# ultrasonic.net
KiCad netlist of a schematic drawn in EAGLE
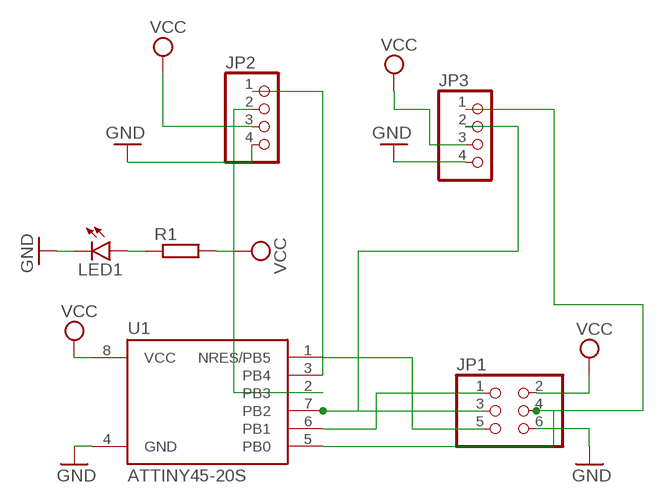
[diagram p0: schematic, sheet 1]

(export (version "E")
  (design (tool "Eeschema 10.0.6"))
  (components
    (comp (ref "JP1")
      (value "PINHD-2X03_2.54-SMD")
      (footprint "eagle-import:2X03SMD")
      (libsource (lib "eagle-import") (part "PINHD-2X03_2.54-SMD"))
    )
    (comp (ref "JP2")
      (value "PINHD-1X04_2.54-SMD")
      (footprint "eagle-import:1X04SMD")
      (libsource (lib "eagle-import") (part "PINHD-1X04_2.54-SMD"))
    )
    (comp (ref "JP3")
      (value "PINHD-1X04_2.54-SMD")
      (footprint "eagle-import:1X04SMD")
      (libsource (lib "eagle-import") (part "PINHD-1X04_2.54-SMD"))
    )
    (comp (ref "LED1")
      (value "LEDCHIPLED_1206")
      (footprint "eagle-import:CHIPLED_1206")
      (libsource (lib "eagle-import") (part "LEDCHIPLED_1206"))
    )
    (comp (ref "R1")
      (value "R-EU_R1206")
      (footprint "eagle-import:R1206")
      (libsource (lib "eagle-import") (part "R-EU_R1206"))
    )
    (comp (ref "U1")
      (value "ATTINY45-20S")
      (footprint "eagle-import:SOIC8_EIAJ_208MIL")
      (libsource (lib "eagle-import") (part "ATTINY45S-20"))
    )
  )
  (nets
    (net (code "1") (name "GND") (class "Default")
      (node (ref "JP1") (pin "6") (pinfunction "6_6") (pintype "passive"))
      (node (ref "JP2") (pin "4") (pinfunction "4_4") (pintype "passive"))
      (node (ref "JP3") (pin "4") (pinfunction "4_4") (pintype "passive"))
      (node (ref "LED1") (pin "C") (pinfunction "C_C") (pintype "passive"))
      (node (ref "U1") (pin "4") (pinfunction "GND_4") (pintype "power_in"))
    )
    (net (code "2") (name "Net-(LED1-PadA)") (class "Default")
      (node (ref "LED1") (pin "A") (pinfunction "A_A") (pintype "passive"))
      (node (ref "R1") (pin "1") (pinfunction "1_1") (pintype "passive"))
    )
    (net (code "3") (name "Net-(U1-NRES{slash}PB5)") (class "Default")
      (node (ref "JP1") (pin "5") (pinfunction "5_5") (pintype "passive"))
      (node (ref "U1") (pin "1") (pinfunction "NRES/PB5_1") (pintype "bidirectional"))
    )
    (net (code "4") (name "Net-(U1-PB0)") (class "Default")
      (node (ref "JP1") (pin "4") (pinfunction "4_4") (pintype "passive"))
      (node (ref "JP3") (pin "1") (pinfunction "1_1") (pintype "passive"))
      (node (ref "U1") (pin "5") (pinfunction "PB0_5") (pintype "bidirectional"))
    )
    (net (code "5") (name "Net-(U1-PB1)") (class "Default")
      (node (ref "JP1") (pin "1") (pinfunction "1_1") (pintype "passive"))
      (node (ref "U1") (pin "6") (pinfunction "PB1_6") (pintype "bidirectional"))
    )
    (net (code "6") (name "Net-(U1-PB2)") (class "Default")
      (node (ref "JP1") (pin "3") (pinfunction "3_3") (pintype "passive"))
      (node (ref "JP3") (pin "2") (pinfunction "2_2") (pintype "passive"))
      (node (ref "U1") (pin "7") (pinfunction "PB2_7") (pintype "bidirectional"))
    )
    (net (code "7") (name "Net-(U1-PB3)") (class "Default")
      (node (ref "JP2") (pin "2") (pinfunction "2_2") (pintype "passive"))
      (node (ref "U1") (pin "2") (pinfunction "PB3_2") (pintype "bidirectional"))
    )
    (net (code "8") (name "Net-(U1-PB4)") (class "Default")
      (node (ref "JP2") (pin "1") (pinfunction "1_1") (pintype "passive"))
      (node (ref "U1") (pin "3") (pinfunction "PB4_3") (pintype "bidirectional"))
    )
    (net (code "9") (name "VCC") (class "Default")
      (node (ref "JP1") (pin "2") (pinfunction "2_2") (pintype "passive"))
      (node (ref "JP2") (pin "3") (pinfunction "3_3") (pintype "passive"))
      (node (ref "JP3") (pin "3") (pinfunction "3_3") (pintype "passive"))
      (node (ref "R1") (pin "2") (pinfunction "2_2") (pintype "passive"))
      (node (ref "U1") (pin "8") (pinfunction "VCC_8") (pintype "power_in"))
    )
  )
)
